# MR-71_RE0.net
KiCad netlist of a schematic drawn in Altium Designer
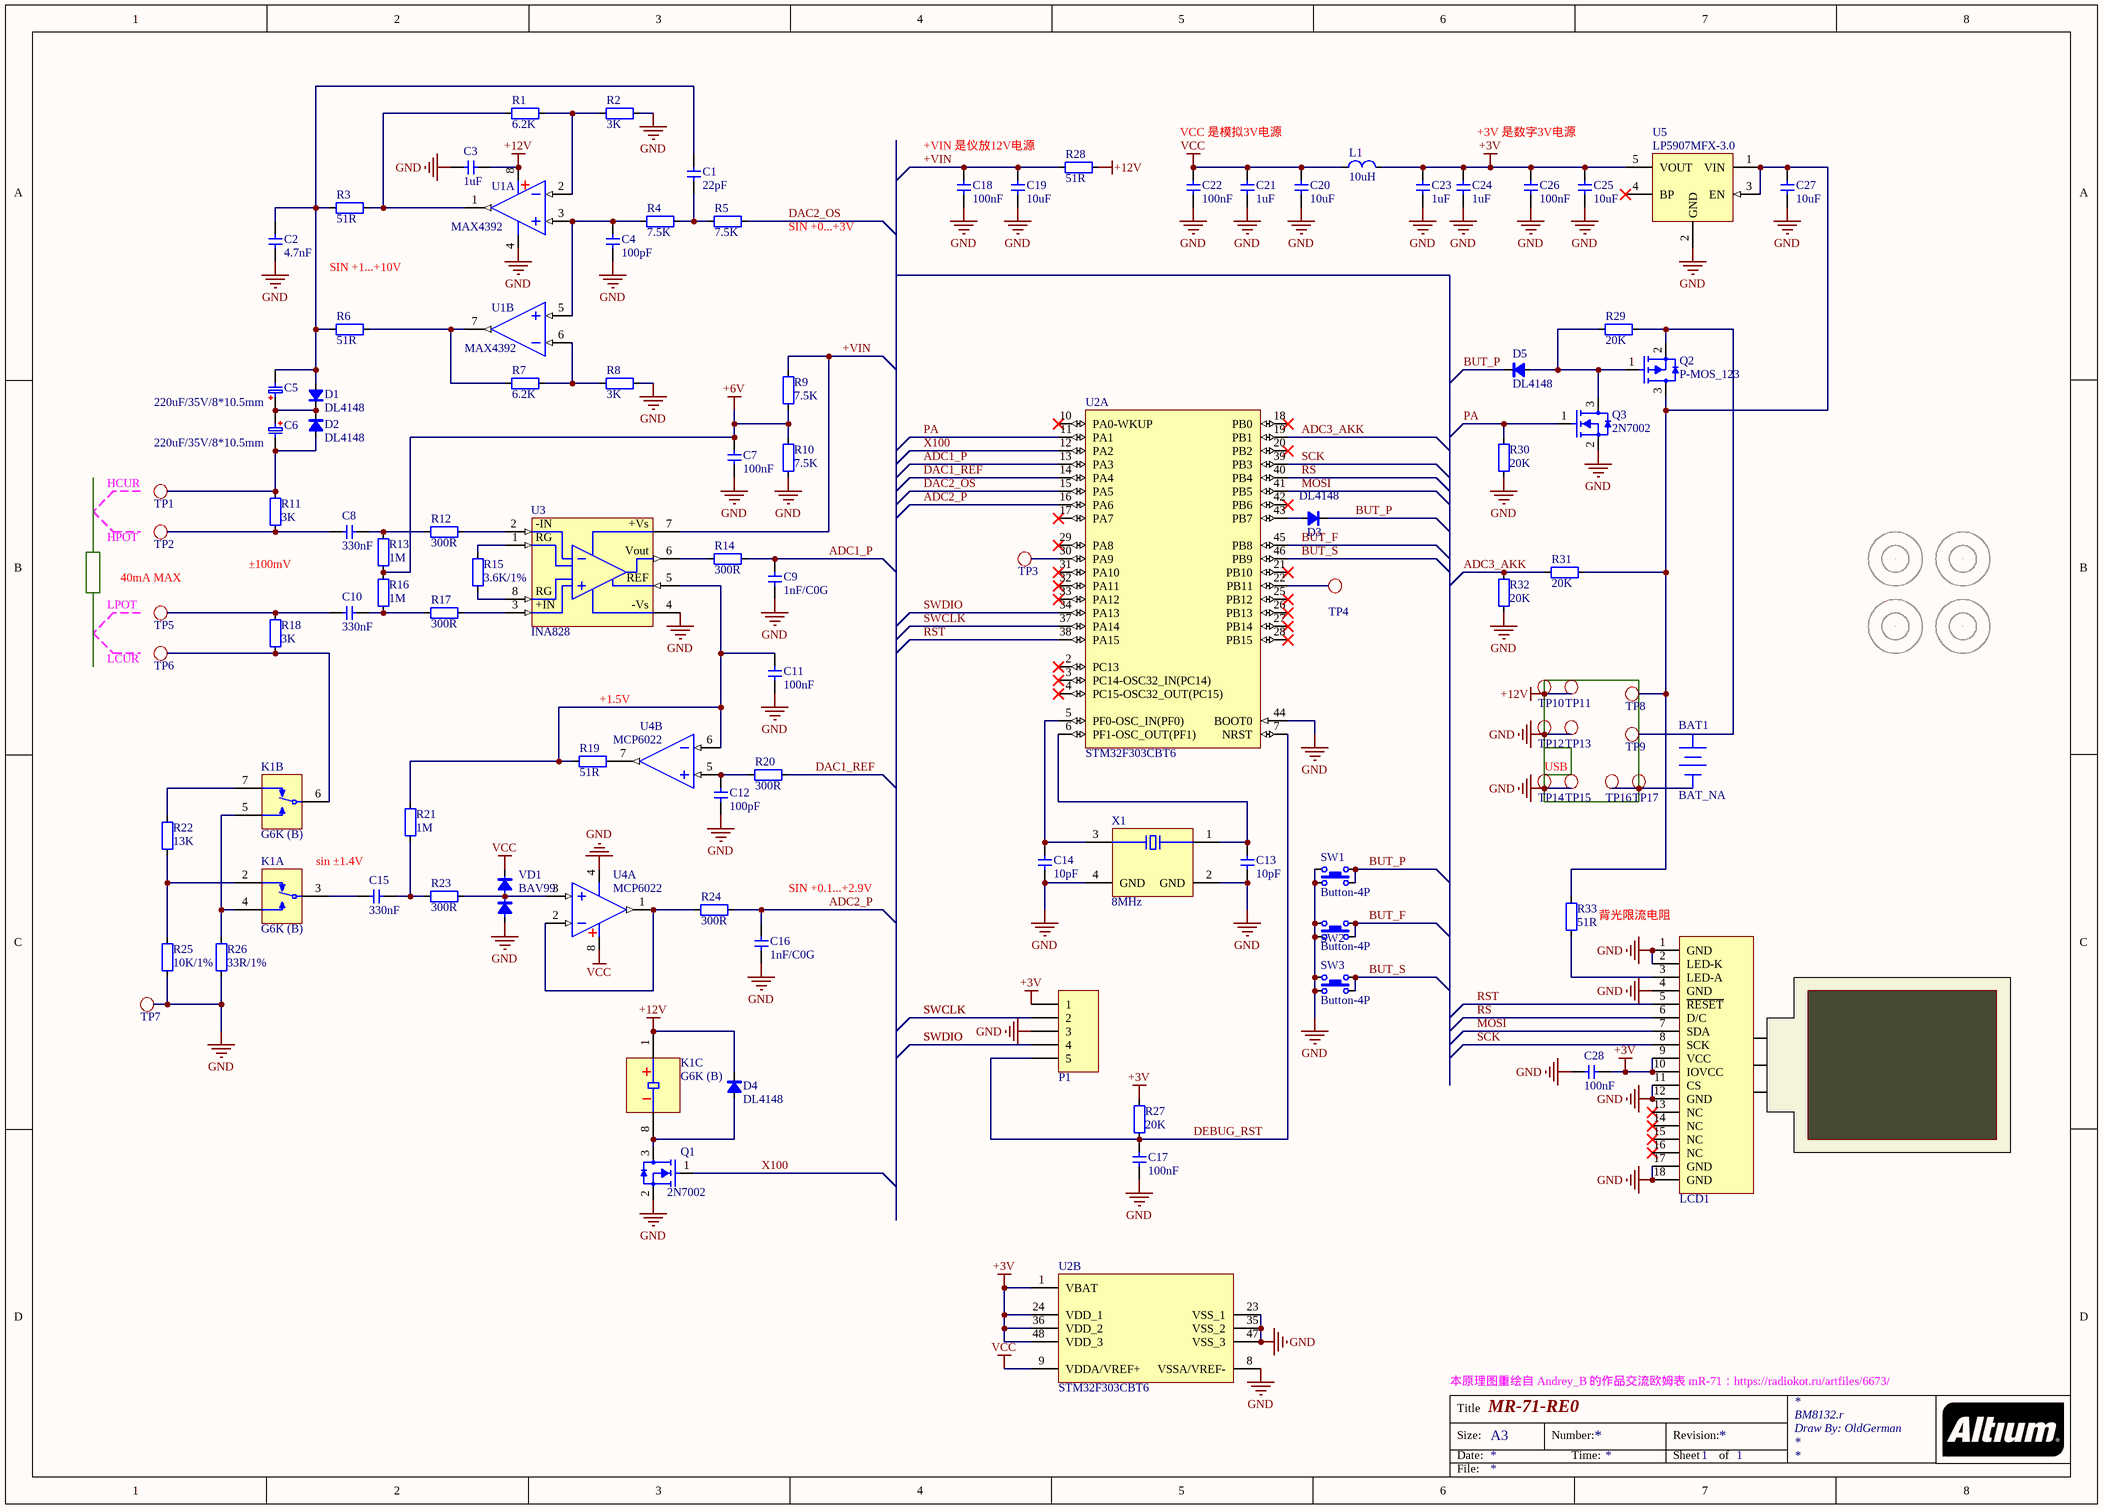
[diagram p0: MR-71_RE0.SchDoc]

(export (version "E")
  (design (tool "Eeschema 10.0.6"))
  (components
    (comp (ref "BAT1")
      (value "BAT_NA")
      (footprint "Lipo_NONE")
      (description "锂电池")
      (libsource (lib "ODG_AD_Lib") (part "BAT_NA"))
    )
    (comp (ref "C1")
      (value "22pF")
      (footprint "C0805")
      (description "Capacitor")
      (libsource (lib "ODG_AD_Lib") (part "CAP"))
    )
    (comp (ref "C2")
      (value "4.7nF")
      (footprint "C0805")
      (description "Capacitor")
      (libsource (lib "ODG_AD_Lib") (part "CAP"))
    )
    (comp (ref "C3")
      (value "1uF")
      (footprint "C0805")
      (description "Capacitor")
      (libsource (lib "ODG_AD_Lib") (part "CAP"))
    )
    (comp (ref "C4")
      (value "100pF")
      (footprint "C0805")
      (description "Capacitor")
      (libsource (lib "ODG_AD_Lib") (part "CAP"))
    )
    (comp (ref "C5")
      (value "220uF/35V/8*10.5mm")
      (footprint "CAP OS-CON D=8.0 L=11.9 E12")
      (description "Capacitor")
      (libsource (lib "ODG_AD_Lib") (part "CAP_Polar_Aluminum"))
    )
    (comp (ref "C6")
      (value "220uF/35V/8*10.5mm")
      (footprint "CAP OS-CON D=8.0 L=11.9 E12")
      (description "Capacitor")
      (libsource (lib "ODG_AD_Lib") (part "CAP_Polar_Aluminum"))
    )
    (comp (ref "C7")
      (value "100nF")
      (footprint "C0805")
      (description "Capacitor")
      (libsource (lib "ODG_AD_Lib") (part "CAP"))
    )
    (comp (ref "C8")
      (value "330nF")
      (footprint "C0805")
      (description "Capacitor")
      (libsource (lib "ODG_AD_Lib") (part "CAP"))
    )
    (comp (ref "C9")
      (value "1nF/C0G")
      (footprint "C0805")
      (description "Capacitor")
      (libsource (lib "ODG_AD_Lib") (part "CAP"))
    )
    (comp (ref "C10")
      (value "330nF")
      (footprint "C0805")
      (description "Capacitor")
      (libsource (lib "ODG_AD_Lib") (part "CAP"))
    )
    (comp (ref "C11")
      (value "100nF")
      (footprint "C0805")
      (description "Capacitor")
      (libsource (lib "ODG_AD_Lib") (part "CAP"))
    )
    (comp (ref "C12")
      (value "100pF")
      (footprint "C0805")
      (description "Capacitor")
      (libsource (lib "ODG_AD_Lib") (part "CAP"))
    )
    (comp (ref "C13")
      (value "10pF")
      (footprint "C0805")
      (description "Capacitor")
      (libsource (lib "ODG_AD_Lib") (part "CAP"))
    )
    (comp (ref "C14")
      (value "10pF")
      (footprint "C0805")
      (description "Capacitor")
      (libsource (lib "ODG_AD_Lib") (part "CAP"))
    )
    (comp (ref "C15")
      (value "330nF")
      (footprint "C0805")
      (description "Capacitor")
      (libsource (lib "ODG_AD_Lib") (part "CAP"))
    )
    (comp (ref "C16")
      (value "1nF/C0G")
      (footprint "C0805")
      (description "Capacitor")
      (libsource (lib "ODG_AD_Lib") (part "CAP"))
    )
    (comp (ref "C17")
      (value "100nF")
      (footprint "C0805")
      (description "Capacitor")
      (libsource (lib "ODG_AD_Lib") (part "CAP"))
    )
    (comp (ref "C18")
      (value "100nF")
      (footprint "C0805")
      (description "Capacitor")
      (libsource (lib "ODG_AD_Lib") (part "CAP"))
    )
    (comp (ref "C19")
      (value "10uF")
      (footprint "C1206")
      (description "Capacitor")
      (libsource (lib "ODG_AD_Lib") (part "CAP"))
    )
    (comp (ref "C20")
      (value "10uF")
      (footprint "C1206")
      (description "Capacitor")
      (libsource (lib "ODG_AD_Lib") (part "CAP"))
    )
    (comp (ref "C21")
      (value "1uF")
      (footprint "C0805")
      (description "Capacitor")
      (libsource (lib "ODG_AD_Lib") (part "CAP"))
    )
    (comp (ref "C22")
      (value "100nF")
      (footprint "C0805")
      (description "Capacitor")
      (libsource (lib "ODG_AD_Lib") (part "CAP"))
    )
    (comp (ref "C23")
      (value "1uF")
      (footprint "C0805")
      (description "Capacitor")
      (libsource (lib "ODG_AD_Lib") (part "CAP"))
    )
    (comp (ref "C24")
      (value "1uF")
      (footprint "C0805")
      (description "Capacitor")
      (libsource (lib "ODG_AD_Lib") (part "CAP"))
    )
    (comp (ref "C25")
      (value "10uF")
      (footprint "C1206")
      (description "Capacitor")
      (libsource (lib "ODG_AD_Lib") (part "CAP"))
    )
    (comp (ref "C26")
      (value "100nF")
      (footprint "C0805")
      (description "Capacitor")
      (libsource (lib "ODG_AD_Lib") (part "CAP"))
    )
    (comp (ref "C27")
      (value "10uF")
      (footprint "C1206")
      (description "Capacitor")
      (libsource (lib "ODG_AD_Lib") (part "CAP"))
    )
    (comp (ref "C28")
      (value "100nF")
      (footprint "C0805")
      (description "Capacitor")
      (libsource (lib "ODG_AD_Lib") (part "CAP"))
    )
    (comp (ref "D1")
      (value "DL4148")
      (footprint "SOD-123")
      (description "二极管")
      (libsource (lib "") (part "DIODE_1"))
    )
    (comp (ref "D2")
      (value "DL4148")
      (footprint "SOD-123")
      (description "二极管")
      (libsource (lib "") (part "DIODE_2"))
    )
    (comp (ref "D3")
      (value "DL4148")
      (footprint "SOD-123")
      (description "二极管")
      (libsource (lib "") (part "DIODE_3"))
    )
    (comp (ref "D4")
      (value "DL4148")
      (footprint "SOD-123")
      (description "二极管")
      (libsource (lib "") (part "DIODE_2"))
    )
    (comp (ref "D5")
      (value "DL4148")
      (footprint "SOD-123")
      (description "二极管")
      (libsource (lib "ODG_AD_Lib") (part "DIODE"))
    )
    (comp (ref "H1") (value "HOLE") (footprint "M3.1 D=5.8 SUN") (libsource (lib "ODG_AD_Lib") (part "HOLE")))
    (comp (ref "H2") (value "HOLE") (footprint "M3.1 D=5.8 SUN") (libsource (lib "ODG_AD_Lib") (part "HOLE")))
    (comp (ref "H3") (value "HOLE") (footprint "M3.1 D=5.8 SUN") (libsource (lib "ODG_AD_Lib") (part "HOLE")))
    (comp (ref "H4") (value "HOLE") (footprint "M3.1 D=5.8 SUN") (libsource (lib "ODG_AD_Lib") (part "HOLE")))
    (comp (ref "K1")
      (value "G6K (B)")
      (footprint "RELAY_G6K-2F-Y")
      (description "Telecom Relay DPDT (2 Form C) Surface Mount")
      (fields (field (name "MF") "Omron Electronics") (field (name "MP") "G6K-2F DC3"))
      (libsource (lib "ODG_AD_Lib") (part "G6K (B)"))
    )
    (comp (ref "L1")
      (value "10uH")
      (footprint "FER0805")
      (description "贴片叠层电感")
      (libsource (lib "ODG_AD_Lib") (part "inductor_mini"))
    )
    (comp (ref "LCD1")
      (value "LCD_Universal_128x160_18pin")
      (footprint "LCD-128X160-1.8INCH_SOLDER_MR-71")
      (libsource (lib "ODG_AD_Lib") (part "LCD_Universal_128x160_18pin"))
    )
    (comp (ref "P1")
      (value "CONN_X5")
      (footprint "2.54MM_MALE_X5")
      (libsource (lib "ODG_AD_Lib") (part "CONN_X5"))
    )
    (comp (ref "Q1")
      (value "2N7002")
      (footprint "INFINEON SOT-23-3")
      (description "N-MOS")
      (libsource (lib "ODG_AD_Lib") (part "N-MOS_123"))
    )
    (comp (ref "Q2")
      (value "P-MOS_123")
      (footprint "INFINEON SOT-23-3")
      (description "P-MOS")
      (libsource (lib "ODG_AD_Lib") (part "P-MOS_123"))
    )
    (comp (ref "Q3")
      (value "2N7002")
      (footprint "INFINEON SOT-23-3")
      (description "N-MOS")
      (libsource (lib "ODG_AD_Lib") (part "N-MOS_123"))
    )
    (comp (ref "R1")
      (value "6.2K")
      (footprint "R0805")
      (description "IEC Standard")
      (libsource (lib "") (part "RES_3"))
    )
    (comp (ref "R2")
      (value "3K")
      (footprint "R0805")
      (description "IEC Standard")
      (libsource (lib "") (part "RES_3"))
    )
    (comp (ref "R3")
      (value "51R")
      (footprint "R0805")
      (description "IEC Standard")
      (libsource (lib "") (part "RES_3"))
    )
    (comp (ref "R4")
      (value "7.5K")
      (footprint "R0805")
      (description "IEC Standard")
      (libsource (lib "") (part "RES_3"))
    )
    (comp (ref "R5")
      (value "7.5K")
      (footprint "R0805")
      (description "IEC Standard")
      (libsource (lib "") (part "RES_3"))
    )
    (comp (ref "R6")
      (value "51R")
      (footprint "R0805")
      (description "IEC Standard")
      (libsource (lib "ODG_AD_Lib") (part "RES"))
    )
    (comp (ref "R7")
      (value "6.2K")
      (footprint "R0805")
      (description "IEC Standard")
      (libsource (lib "ODG_AD_Lib") (part "RES"))
    )
    (comp (ref "R8")
      (value "3K")
      (footprint "R0805")
      (description "IEC Standard")
      (libsource (lib "ODG_AD_Lib") (part "RES"))
    )
    (comp (ref "R9")
      (value "7.5K")
      (footprint "R0805")
      (description "IEC Standard")
      (libsource (lib "ODG_AD_Lib") (part "RES"))
    )
    (comp (ref "R10")
      (value "7.5K")
      (footprint "R0805")
      (description "IEC Standard")
      (libsource (lib "ODG_AD_Lib") (part "RES"))
    )
    (comp (ref "R11")
      (value "3K")
      (footprint "R0805")
      (description "IEC Standard")
      (libsource (lib "") (part "RES_2"))
    )
    (comp (ref "R12")
      (value "300R")
      (footprint "R0805")
      (description "IEC Standard")
      (libsource (lib "") (part "RES_1"))
    )
    (comp (ref "R13")
      (value "1M")
      (footprint "R0805")
      (description "IEC Standard")
      (libsource (lib "") (part "RES_2"))
    )
    (comp (ref "R14")
      (value "300R")
      (footprint "R0805")
      (description "IEC Standard")
      (libsource (lib "") (part "RES_1"))
    )
    (comp (ref "R15")
      (value "3.6K/1%")
      (footprint "R0805")
      (description "IEC Standard")
      (libsource (lib "") (part "RES_2"))
    )
    (comp (ref "R16")
      (value "1M")
      (footprint "R0805")
      (description "IEC Standard")
      (libsource (lib "") (part "RES_2"))
    )
    (comp (ref "R17")
      (value "300R")
      (footprint "R0805")
      (description "IEC Standard")
      (libsource (lib "") (part "RES_1"))
    )
    (comp (ref "R18")
      (value "3K")
      (footprint "R0805")
      (description "IEC Standard")
      (libsource (lib "") (part "RES_2"))
    )
    (comp (ref "R19")
      (value "51R")
      (footprint "R0805")
      (description "IEC Standard")
      (libsource (lib "ODG_AD_Lib") (part "RES"))
    )
    (comp (ref "R20")
      (value "300R")
      (footprint "R0805")
      (description "IEC Standard")
      (libsource (lib "") (part "RES_1"))
    )
    (comp (ref "R21")
      (value "1M")
      (footprint "R0805")
      (description "IEC Standard")
      (libsource (lib "") (part "RES_2"))
    )
    (comp (ref "R22")
      (value "13K")
      (footprint "R0805")
      (description "IEC Standard")
      (libsource (lib "") (part "RES_2"))
    )
    (comp (ref "R23")
      (value "300R")
      (footprint "R0805")
      (description "IEC Standard")
      (libsource (lib "") (part "RES_1"))
    )
    (comp (ref "R24")
      (value "300R")
      (footprint "R0805")
      (description "IEC Standard")
      (libsource (lib "") (part "RES_1"))
    )
    (comp (ref "R25")
      (value "10K/1%")
      (footprint "R0805")
      (description "IEC Standard")
      (libsource (lib "") (part "RES_2"))
    )
    (comp (ref "R26")
      (value "33R/1%")
      (footprint "R1206")
      (description "IEC Standard")
      (libsource (lib "") (part "RES_2"))
    )
    (comp (ref "R27")
      (value "20K")
      (footprint "R0805")
      (description "IEC Standard")
      (libsource (lib "") (part "RES_3"))
    )
    (comp (ref "R28")
      (value "51R")
      (footprint "R0805")
      (description "IEC Standard")
      (libsource (lib "ODG_AD_Lib") (part "RES"))
    )
    (comp (ref "R29")
      (value "20K")
      (footprint "R0805")
      (description "IEC Standard")
      (libsource (lib "ODG_AD_Lib") (part "RES"))
    )
    (comp (ref "R30")
      (value "20K")
      (footprint "R0805")
      (description "IEC Standard")
      (libsource (lib "") (part "RES_2"))
    )
    (comp (ref "R31")
      (value "20K")
      (footprint "R0805")
      (description "IEC Standard")
      (libsource (lib "ODG_AD_Lib") (part "RES"))
    )
    (comp (ref "R32")
      (value "20K")
      (footprint "R0805")
      (description "IEC Standard")
      (libsource (lib "") (part "RES_2"))
    )
    (comp (ref "R33")
      (value "51R")
      (footprint "R0805")
      (description "IEC Standard")
      (libsource (lib "") (part "RES_3"))
    )
    (comp (ref "SW1")
      (value "Button-4P")
      (footprint "TACTILE_SWITCH_SMD_4X4MM")
      (description "Button")
      (libsource (lib "ODG_AD_Lib") (part "Button-4P"))
    )
    (comp (ref "SW2")
      (value "Button-4P")
      (footprint "TACTILE_SWITCH_SMD_4X4MM")
      (description "Button")
      (libsource (lib "ODG_AD_Lib") (part "Button-4P"))
    )
    (comp (ref "SW3")
      (value "Button-4P")
      (footprint "TACTILE_SWITCH_SMD_4X4MM")
      (description "Button")
      (libsource (lib "ODG_AD_Lib") (part "Button-4P"))
    )
    (comp (ref "TP1")
      (value "TP_SMD")
      (footprint "TP_SMD_1.5mm_01")
      (description "SMD testpad")
      (libsource (lib "ODG_AD_Lib") (part "TP_SMD"))
    )
    (comp (ref "TP2")
      (value "TP_SMD")
      (footprint "TP_SMD_1.5mm_01")
      (description "SMD testpad")
      (libsource (lib "ODG_AD_Lib") (part "TP_SMD"))
    )
    (comp (ref "TP3")
      (value "TP_SMD")
      (footprint "TP_SMD_1.5mm_01")
      (description "SMD testpad")
      (libsource (lib "ODG_AD_Lib") (part "TP_SMD"))
    )
    (comp (ref "TP4")
      (value "TP_SMD")
      (footprint "TP_SMD_1.5mm_01")
      (description "SMD testpad")
      (libsource (lib "ODG_AD_Lib") (part "TP_SMD"))
    )
    (comp (ref "TP5")
      (value "TP_SMD")
      (footprint "TP_SMD_1.5mm_01")
      (description "SMD testpad")
      (libsource (lib "ODG_AD_Lib") (part "TP_SMD"))
    )
    (comp (ref "TP6")
      (value "TP_SMD")
      (footprint "TP_SMD_1.5mm_01")
      (description "SMD testpad")
      (libsource (lib "ODG_AD_Lib") (part "TP_SMD"))
    )
    (comp (ref "TP7")
      (value "TP_SMD")
      (footprint "TP_SMD_1.5mm_01")
      (description "SMD testpad")
      (libsource (lib "ODG_AD_Lib") (part "TP_SMD"))
    )
    (comp (ref "TP8")
      (value "TP_SMD")
      (footprint "TP_SMD_1.5mm_01")
      (description "SMD testpad")
      (libsource (lib "ODG_AD_Lib") (part "TP_SMD"))
    )
    (comp (ref "TP9")
      (value "TP_SMD")
      (footprint "TP_SMD_1.5mm_01")
      (description "SMD testpad")
      (libsource (lib "ODG_AD_Lib") (part "TP_SMD"))
    )
    (comp (ref "TP10")
      (value "TP_SMD")
      (footprint "KEYSTONE_5015")
      (description "SMD testpad")
      (libsource (lib "ODG_AD_Lib") (part "TP_SMD"))
    )
    (comp (ref "TP11")
      (value "TP_SMD")
      (footprint "KEYSTONE_5015")
      (description "SMD testpad")
      (libsource (lib "ODG_AD_Lib") (part "TP_SMD"))
    )
    (comp (ref "TP12")
      (value "TP_SMD")
      (footprint "KEYSTONE_5015")
      (description "SMD testpad")
      (libsource (lib "ODG_AD_Lib") (part "TP_SMD"))
    )
    (comp (ref "TP13")
      (value "TP_SMD")
      (footprint "KEYSTONE_5015")
      (description "SMD testpad")
      (libsource (lib "ODG_AD_Lib") (part "TP_SMD"))
    )
    (comp (ref "TP14")
      (value "TP_SMD")
      (footprint "KEYSTONE_5015")
      (description "SMD testpad")
      (libsource (lib "ODG_AD_Lib") (part "TP_SMD"))
    )
    (comp (ref "TP15")
      (value "TP_SMD")
      (footprint "KEYSTONE_5015")
      (description "SMD testpad")
      (libsource (lib "ODG_AD_Lib") (part "TP_SMD"))
    )
    (comp (ref "TP16")
      (value "TP_SMD")
      (footprint "KEYSTONE_5015")
      (description "SMD testpad")
      (libsource (lib "ODG_AD_Lib") (part "TP_SMD"))
    )
    (comp (ref "TP17")
      (value "TP_SMD")
      (footprint "KEYSTONE_5015")
      (description "SMD testpad")
      (libsource (lib "ODG_AD_Lib") (part "TP_SMD"))
    )
    (comp (ref "U1")
      (value "MAX4392")
      (footprint "ANALOG DEV SOIC-8 R8")
      (description "通用型CMOS双路轨到轨放大器\r\nGeneral-Purpose CMOS Dual Rail-to-Rail Amplifier")
      (libsource (lib "ODG_AD_Lib") (part "AD8542"))
    )
    (comp (ref "U2")
      (value "STM32F303CBT6")
      (footprint "ST LQFP-48 7x7MM")
      (description "带DSP和FPU的主流混合信号ARM Cortex-M4 MCU，具有128 KB Flash、72 MHz CPU、MPU、CCM、5 MSPS 12位ADC、PGA和比较器")
      (fields (field (name "PARTNUMBER") "STM32F103CBT6"))
      (libsource (lib "ODG_AD_Lib") (part "STM32F303CBT6"))
    )
    (comp (ref "U3")
      (value "INA828")
      (footprint "ANALOG DEV SOIC-8 R8")
      (description "50-µV Offset, 7-nV/√Hz Noise, Low-Power, Precision Instrumentation Amplifier")
      (libsource (lib "ODG_AD_Lib") (part "INA828"))
    )
    (comp (ref "U4")
      (value "MCP6022")
      (footprint "ANALOG DEV SOIC-8 R8")
      (libsource (lib "ODG_AD_Lib") (part "AD8542"))
    )
    (comp (ref "U5")
      (value "LP5907MFX-3.0")
      (footprint "ANALOG TSOT-23-5 UJ-5")
      (description "超低噪声线性稳压芯片")
      (libsource (lib "ODG_AD_Lib") (part "ADP150AUJZ-3.3-R7"))
    )
    (comp (ref "VD1")
      (value "BAV99")
      (footprint "INFINEON SOT-23-3")
      (description "Dual Series Switching Diodes")
      (libsource (lib "ODG_AD_Lib") (part "BAV99"))
    )
    (comp (ref "X1")
      (value "8MHz")
      (footprint "EPSON TSX-3225")
      (description "4脚无源石英晶振")
      (libsource (lib "ODG_AD_Lib") (part "XTAL-4P_crystal"))
    )
  )
  (nets
    (net (code "1") (name "+3V") (class "Default")
      (node (ref "C23") (pin "1") (pinfunction "1_1") (pintype "passive"))
      (node (ref "C24") (pin "1") (pinfunction "1_1") (pintype "passive"))
      (node (ref "C25") (pin "1") (pinfunction "1_1") (pintype "passive"))
      (node (ref "C26") (pin "1") (pinfunction "1_1") (pintype "passive"))
      (node (ref "C28") (pin "2") (pinfunction "2_2") (pintype "passive"))
      (node (ref "L1") (pin "2") (pinfunction "2_2") (pintype "passive"))
      (node (ref "LCD1") (pin "10") (pinfunction "IOVCC_10") (pintype "passive"))
      (node (ref "LCD1") (pin "9") (pinfunction "VCC_9") (pintype "passive"))
      (node (ref "P1") (pin "1") (pinfunction "1_1") (pintype "passive"))
      (node (ref "R27") (pin "2") (pinfunction "2_2") (pintype "passive"))
      (node (ref "U2") (pin "1") (pinfunction "VBAT_1") (pintype "power_in"))
      (node (ref "U2") (pin "24") (pinfunction "VDD_1_24") (pintype "power_in"))
      (node (ref "U2") (pin "36") (pinfunction "VDD_2_36") (pintype "power_in"))
      (node (ref "U2") (pin "48") (pinfunction "VDD_3_48") (pintype "power_in"))
      (node (ref "U5") (pin "5") (pinfunction "VOUT_5") (pintype "passive"))
    )
    (net (code "2") (name "+6V") (class "Default")
      (node (ref "C7") (pin "1") (pinfunction "1_1") (pintype "passive"))
      (node (ref "R10") (pin "2") (pinfunction "2_2") (pintype "passive"))
      (node (ref "R13") (pin "2") (pinfunction "2_2") (pintype "passive"))
      (node (ref "R16") (pin "1") (pinfunction "1_1") (pintype "passive"))
      (node (ref "R9") (pin "1") (pinfunction "1_1") (pintype "passive"))
    )
    (net (code "3") (name "+12V") (class "Default")
      (node (ref "C3") (pin "2") (pinfunction "2_2") (pintype "passive"))
      (node (ref "D4") (pin "2") (pinfunction "C_2") (pintype "passive"))
      (node (ref "K1") (pin "1") (pinfunction "1_1") (pintype "passive"))
      (node (ref "R28") (pin "2") (pinfunction "2_2") (pintype "passive"))
      (node (ref "TP10") (pin "1") (pinfunction "1_1") (pintype "passive"))
      (node (ref "TP11") (pin "1") (pinfunction "1_1") (pintype "passive"))
      (node (ref "U1") (pin "8") (pinfunction "V+_8") (pintype "power_in"))
    )
    (net (code "4") (name "/+VIN") (class "Default")
      (node (ref "C18") (pin "1") (pinfunction "1_1") (pintype "passive"))
      (node (ref "C19") (pin "1") (pinfunction "1_1") (pintype "passive"))
      (node (ref "R28") (pin "1") (pinfunction "1_1") (pintype "passive"))
      (node (ref "R9") (pin "2") (pinfunction "2_2") (pintype "passive"))
      (node (ref "U3") (pin "7") (pinfunction "+Vs_7") (pintype "passive"))
    )
    (net (code "5") (name "/ADC1_P") (class "Default")
      (node (ref "C9") (pin "1") (pinfunction "1_1") (pintype "passive"))
      (node (ref "R14") (pin "1") (pinfunction "1_1") (pintype "passive"))
      (node (ref "U2") (pin "13") (pinfunction "PA3_13") (pintype "bidirectional"))
    )
    (net (code "6") (name "/ADC2_P") (class "Default")
      (node (ref "C16") (pin "2") (pinfunction "2_2") (pintype "passive"))
      (node (ref "R24") (pin "1") (pinfunction "1_1") (pintype "passive"))
      (node (ref "U2") (pin "16") (pinfunction "PA6_16") (pintype "bidirectional"))
    )
    (net (code "7") (name "/ADC3_AKK") (class "Default")
      (node (ref "R31") (pin "1") (pinfunction "1_1") (pintype "passive"))
      (node (ref "R32") (pin "1") (pinfunction "1_1") (pintype "passive"))
      (node (ref "U2") (pin "19") (pinfunction "PB1_19") (pintype "bidirectional"))
    )
    (net (code "8") (name "/BUT_F") (class "Default")
      (node (ref "SW2") (pin "3") (pinfunction "3_3") (pintype "passive"))
      (node (ref "SW2") (pin "4") (pinfunction "4_4") (pintype "passive"))
      (node (ref "U2") (pin "45") (pinfunction "PB8_45") (pintype "bidirectional"))
    )
    (net (code "9") (name "/BUT_P") (class "Default")
      (node (ref "D3") (pin "2") (pinfunction "C_2") (pintype "passive"))
      (node (ref "D5") (pin "2") (pinfunction "C_2") (pintype "passive"))
      (node (ref "SW1") (pin "3") (pinfunction "3_3") (pintype "passive"))
      (node (ref "SW1") (pin "4") (pinfunction "4_4") (pintype "passive"))
    )
    (net (code "10") (name "/BUT_S") (class "Default")
      (node (ref "SW3") (pin "3") (pinfunction "3_3") (pintype "passive"))
      (node (ref "SW3") (pin "4") (pinfunction "4_4") (pintype "passive"))
      (node (ref "U2") (pin "46") (pinfunction "PB9_46") (pintype "bidirectional"))
    )
    (net (code "11") (name "/DAC1_REF") (class "Default")
      (node (ref "R20") (pin "1") (pinfunction "1_1") (pintype "passive"))
      (node (ref "U2") (pin "14") (pinfunction "PA4_14") (pintype "bidirectional"))
    )
    (net (code "12") (name "/DAC2_OS") (class "Default")
      (node (ref "R5") (pin "2") (pinfunction "2_2") (pintype "passive"))
      (node (ref "U2") (pin "15") (pinfunction "PA5_15") (pintype "bidirectional"))
    )
    (net (code "13") (name "/DEBUG_RST") (class "Default")
      (node (ref "C17") (pin "2") (pinfunction "2_2") (pintype "passive"))
      (node (ref "P1") (pin "5") (pinfunction "5_5") (pintype "passive"))
      (node (ref "R27") (pin "1") (pinfunction "1_1") (pintype "passive"))
      (node (ref "U2") (pin "7") (pinfunction "NRST_7") (pintype "bidirectional"))
    )
    (net (code "14") (name "/MOSI") (class "Default")
      (node (ref "LCD1") (pin "7") (pinfunction "SDA_7") (pintype "passive"))
      (node (ref "U2") (pin "41") (pinfunction "PB5_41") (pintype "bidirectional"))
    )
    (net (code "15") (name "/PA") (class "Default")
      (node (ref "Q3") (pin "1") (pinfunction "G_1") (pintype "passive"))
      (node (ref "R30") (pin "1") (pinfunction "1_1") (pintype "passive"))
      (node (ref "U2") (pin "11") (pinfunction "PA1_11") (pintype "bidirectional"))
    )
    (net (code "16") (name "/RS") (class "Default")
      (node (ref "LCD1") (pin "6") (pinfunction "D/C_6") (pintype "passive"))
      (node (ref "U2") (pin "40") (pinfunction "PB4_40") (pintype "bidirectional"))
    )
    (net (code "17") (name "/RST") (class "Default")
      (node (ref "LCD1") (pin "5") (pinfunction "~{RESET}_5") (pintype "passive"))
      (node (ref "U2") (pin "38") (pinfunction "PA15_38") (pintype "bidirectional"))
    )
    (net (code "18") (name "/SCK") (class "Default")
      (node (ref "LCD1") (pin "8") (pinfunction "SCK_8") (pintype "passive"))
      (node (ref "U2") (pin "39") (pinfunction "PB3_39") (pintype "bidirectional"))
    )
    (net (code "19") (name "/SWCLK") (class "Default")
      (node (ref "P1") (pin "2") (pinfunction "2_2") (pintype "passive"))
      (node (ref "U2") (pin "37") (pinfunction "PA14_37") (pintype "bidirectional"))
    )
    (net (code "20") (name "/SWDIO") (class "Default")
      (node (ref "P1") (pin "4") (pinfunction "4_4") (pintype "passive"))
      (node (ref "U2") (pin "34") (pinfunction "PA13_34") (pintype "bidirectional"))
    )
    (net (code "21") (name "/X100") (class "Default")
      (node (ref "Q1") (pin "1") (pinfunction "G_1") (pintype "passive"))
      (node (ref "U2") (pin "12") (pinfunction "PA2_12") (pintype "bidirectional"))
    )
    (net (code "22") (name "GND") (class "Default")
      (node (ref "C11") (pin "2") (pinfunction "2_2") (pintype "passive"))
      (node (ref "C12") (pin "2") (pinfunction "2_2") (pintype "passive"))
      (node (ref "C13") (pin "1") (pinfunction "1_1") (pintype "passive"))
      (node (ref "C14") (pin "1") (pinfunction "1_1") (pintype "passive"))
      (node (ref "C16") (pin "1") (pinfunction "1_1") (pintype "passive"))
      (node (ref "C17") (pin "1") (pinfunction "1_1") (pintype "passive"))
      (node (ref "C18") (pin "2") (pinfunction "2_2") (pintype "passive"))
      (node (ref "C19") (pin "2") (pinfunction "2_2") (pintype "passive"))
      (node (ref "C2") (pin "2") (pinfunction "2_2") (pintype "passive"))
      (node (ref "C20") (pin "2") (pinfunction "2_2") (pintype "passive"))
      (node (ref "C21") (pin "2") (pinfunction "2_2") (pintype "passive"))
      (node (ref "C22") (pin "2") (pinfunction "2_2") (pintype "passive"))
      (node (ref "C23") (pin "2") (pinfunction "2_2") (pintype "passive"))
      (node (ref "C24") (pin "2") (pinfunction "2_2") (pintype "passive"))
      (node (ref "C25") (pin "2") (pinfunction "2_2") (pintype "passive"))
      (node (ref "C26") (pin "2") (pinfunction "2_2") (pintype "passive"))
      (node (ref "C27") (pin "2") (pinfunction "2_2") (pintype "passive"))
      (node (ref "C28") (pin "1") (pinfunction "1_1") (pintype "passive"))
      (node (ref "C3") (pin "1") (pinfunction "1_1") (pintype "passive"))
      (node (ref "C4") (pin "2") (pinfunction "2_2") (pintype "passive"))
      (node (ref "C7") (pin "2") (pinfunction "2_2") (pintype "passive"))
      (node (ref "C9") (pin "2") (pinfunction "2_2") (pintype "passive"))
      (node (ref "LCD1") (pin "1") (pinfunction "GND_1") (pintype "passive"))
      (node (ref "LCD1") (pin "11") (pinfunction "CS_11") (pintype "passive"))
      (node (ref "LCD1") (pin "12") (pinfunction "GND_12") (pintype "passive"))
      (node (ref "LCD1") (pin "17") (pinfunction "GND_17") (pintype "passive"))
      (node (ref "LCD1") (pin "18") (pinfunction "GND_18") (pintype "passive"))
      (node (ref "LCD1") (pin "2") (pinfunction "LED-K_2") (pintype "passive"))
      (node (ref "LCD1") (pin "4") (pinfunction "GND_4") (pintype "passive"))
      (node (ref "P1") (pin "3") (pinfunction "3_3") (pintype "passive"))
      (node (ref "Q1") (pin "2") (pinfunction "S_2") (pintype "passive"))
      (node (ref "Q3") (pin "2") (pinfunction "S_2") (pintype "passive"))
      (node (ref "R10") (pin "1") (pinfunction "1_1") (pintype "passive"))
      (node (ref "R2") (pin "2") (pinfunction "2_2") (pintype "passive"))
      (node (ref "R25") (pin "2") (pinfunction "2_2") (pintype "passive"))
      (node (ref "R26") (pin "2") (pinfunction "2_2") (pintype "passive"))
      (node (ref "R30") (pin "2") (pinfunction "2_2") (pintype "passive"))
      (node (ref "R32") (pin "2") (pinfunction "2_2") (pintype "passive"))
      (node (ref "R8") (pin "2") (pinfunction "2_2") (pintype "passive"))
      (node (ref "SW1") (pin "1") (pinfunction "1_1") (pintype "passive"))
      (node (ref "SW1") (pin "2") (pinfunction "2_2") (pintype "passive"))
      (node (ref "SW2") (pin "1") (pinfunction "1_1") (pintype "passive"))
      (node (ref "SW2") (pin "2") (pinfunction "2_2") (pintype "passive"))
      (node (ref "SW3") (pin "1") (pinfunction "1_1") (pintype "passive"))
      (node (ref "SW3") (pin "2") (pinfunction "2_2") (pintype "passive"))
      (node (ref "TP12") (pin "1") (pinfunction "1_1") (pintype "passive"))
      (node (ref "TP13") (pin "1") (pinfunction "1_1") (pintype "passive"))
      (node (ref "TP14") (pin "1") (pinfunction "1_1") (pintype "passive"))
      (node (ref "TP15") (pin "1") (pinfunction "1_1") (pintype "passive"))
      (node (ref "TP7") (pin "1") (pinfunction "1_1") (pintype "passive"))
      (node (ref "U1") (pin "4") (pinfunction "V-_4") (pintype "power_in"))
      (node (ref "U2") (pin "23") (pinfunction "VSS_1_23") (pintype "power_in"))
      (node (ref "U2") (pin "35") (pinfunction "VSS_2_35") (pintype "power_in"))
      (node (ref "U2") (pin "44") (pinfunction "BOOT0_44") (pintype "input"))
      (node (ref "U2") (pin "47") (pinfunction "VSS_3_47") (pintype "power_in"))
      (node (ref "U2") (pin "8") (pinfunction "VSSA/VREF-_8") (pintype "power_in"))
      (node (ref "U3") (pin "4") (pinfunction "-Vs_4") (pintype "passive"))
      (node (ref "U4") (pin "4") (pinfunction "V-_4") (pintype "power_in"))
      (node (ref "U5") (pin "2") (pinfunction "GND_2") (pintype "passive"))
      (node (ref "VD1") (pin "1") (pinfunction "1_1") (pintype "passive"))
      (node (ref "X1") (pin "2") (pinfunction "GND_2") (pintype "passive"))
      (node (ref "X1") (pin "4") (pinfunction "GND_4") (pintype "passive"))
    )
    (net (code "23") (name "Net-(C1-Pad2)") (class "Default")
      (node (ref "C1") (pin "2") (pinfunction "2_2") (pintype "passive"))
      (node (ref "R4") (pin "2") (pinfunction "2_2") (pintype "passive"))
      (node (ref "R5") (pin "1") (pinfunction "1_1") (pintype "passive"))
    )
    (net (code "24") (name "Net-(C8-Pad1)") (class "Default")
      (node (ref "C8") (pin "1") (pinfunction "1_1") (pintype "passive"))
      (node (ref "R12") (pin "2") (pinfunction "2_2") (pintype "passive"))
      (node (ref "R13") (pin "1") (pinfunction "1_1") (pintype "passive"))
    )
    (net (code "25") (name "Net-(C8-Pad2)") (class "Default")
      (node (ref "C8") (pin "2") (pinfunction "2_2") (pintype "passive"))
      (node (ref "R11") (pin "2") (pinfunction "2_2") (pintype "passive"))
      (node (ref "TP2") (pin "1") (pinfunction "1_1") (pintype "passive"))
    )
    (net (code "26") (name "Net-(C10-Pad1)") (class "Default")
      (node (ref "C10") (pin "1") (pinfunction "1_1") (pintype "passive"))
      (node (ref "R16") (pin "2") (pinfunction "2_2") (pintype "passive"))
      (node (ref "R17") (pin "2") (pinfunction "2_2") (pintype "passive"))
    )
    (net (code "27") (name "Net-(C10-Pad2)") (class "Default")
      (node (ref "C10") (pin "2") (pinfunction "2_2") (pintype "passive"))
      (node (ref "R18") (pin "1") (pinfunction "1_1") (pintype "passive"))
      (node (ref "TP5") (pin "1") (pinfunction "1_1") (pintype "passive"))
    )
    (net (code "28") (name "Net-(C15-Pad1)") (class "Default")
      (node (ref "C15") (pin "1") (pinfunction "1_1") (pintype "passive"))
      (node (ref "R21") (pin "2") (pinfunction "2_2") (pintype "passive"))
      (node (ref "R23") (pin "2") (pinfunction "2_2") (pintype "passive"))
    )
    (net (code "29") (name "Net-(C15-Pad2)") (class "Default")
      (node (ref "C15") (pin "2") (pinfunction "2_2") (pintype "passive"))
      (node (ref "K1") (pin "3") (pinfunction "3_3") (pintype "passive"))
    )
    (net (code "30") (name "Net-(D1-A)") (class "Default")
      (node (ref "C1") (pin "1") (pinfunction "1_1") (pintype "passive"))
      (node (ref "C2") (pin "1") (pinfunction "1_1") (pintype "passive"))
      (node (ref "C5") (pin "2") (pinfunction "2_2") (pintype "passive"))
      (node (ref "D1") (pin "1") (pinfunction "A_1") (pintype "passive"))
      (node (ref "R3") (pin "1") (pinfunction "1_1") (pintype "passive"))
      (node (ref "R6") (pin "1") (pinfunction "1_1") (pintype "passive"))
    )
    (net (code "31") (name "Net-(D1-C)") (class "Default")
      (node (ref "C5") (pin "1") (pinfunction "1_1") (pintype "passive"))
      (node (ref "C6") (pin "1") (pinfunction "1_1") (pintype "passive"))
      (node (ref "D1") (pin "2") (pinfunction "C_2") (pintype "passive"))
      (node (ref "D2") (pin "2") (pinfunction "C_2") (pintype "passive"))
    )
    (net (code "32") (name "Net-(D2-A)") (class "Default")
      (node (ref "C6") (pin "2") (pinfunction "2_2") (pintype "passive"))
      (node (ref "D2") (pin "1") (pinfunction "A_1") (pintype "passive"))
      (node (ref "R11") (pin "1") (pinfunction "1_1") (pintype "passive"))
      (node (ref "TP1") (pin "1") (pinfunction "1_1") (pintype "passive"))
    )
    (net (code "33") (name "Net-(D3-A)") (class "Default")
      (node (ref "D3") (pin "1") (pinfunction "A_1") (pintype "passive"))
      (node (ref "U2") (pin "43") (pinfunction "PB7_43") (pintype "bidirectional"))
    )
    (net (code "34") (name "Net-(D4-A)") (class "Default")
      (node (ref "D4") (pin "1") (pinfunction "A_1") (pintype "passive"))
      (node (ref "K1") (pin "8") (pinfunction "8_8") (pintype "passive"))
      (node (ref "Q1") (pin "3") (pinfunction "D_3") (pintype "passive"))
    )
    (net (code "35") (name "Net-(D5-A)") (class "Default")
      (node (ref "D5") (pin "1") (pinfunction "A_1") (pintype "passive"))
      (node (ref "Q2") (pin "1") (pinfunction "G_1") (pintype "passive"))
      (node (ref "Q3") (pin "3") (pinfunction "D_3") (pintype "passive"))
      (node (ref "R29") (pin "1") (pinfunction "1_1") (pintype "passive"))
    )
    (net (code "36") (name "Net-(K1-Pad2)") (class "Default")
      (node (ref "K1") (pin "2") (pinfunction "2_2") (pintype "passive"))
      (node (ref "R22") (pin "2") (pinfunction "2_2") (pintype "passive"))
      (node (ref "R25") (pin "1") (pinfunction "1_1") (pintype "passive"))
    )
    (net (code "37") (name "Net-(K1-Pad4)") (class "Default")
      (node (ref "K1") (pin "4") (pinfunction "4_4") (pintype "passive"))
      (node (ref "K1") (pin "5") (pinfunction "5_5") (pintype "passive"))
      (node (ref "R26") (pin "1") (pinfunction "1_1") (pintype "passive"))
    )
    (net (code "38") (name "Net-(K1-Pad6)") (class "Default")
      (node (ref "K1") (pin "6") (pinfunction "6_6") (pintype "passive"))
      (node (ref "R18") (pin "2") (pinfunction "2_2") (pintype "passive"))
      (node (ref "TP6") (pin "1") (pinfunction "1_1") (pintype "passive"))
    )
    (net (code "39") (name "Net-(K1-Pad7)") (class "Default")
      (node (ref "K1") (pin "7") (pinfunction "7_7") (pintype "passive"))
      (node (ref "R22") (pin "1") (pinfunction "1_1") (pintype "passive"))
    )
    (net (code "40") (name "Net-(LCD1-LED-A)") (class "Default")
      (node (ref "LCD1") (pin "3") (pinfunction "LED-A_3") (pintype "passive"))
      (node (ref "R33") (pin "1") (pinfunction "1_1") (pintype "passive"))
    )
    (net (code "41") (name "Net-(Q2-D)") (class "Default")
      (node (ref "C27") (pin "1") (pinfunction "1_1") (pintype "passive"))
      (node (ref "Q2") (pin "3") (pinfunction "D_3") (pintype "passive"))
      (node (ref "R31") (pin "2") (pinfunction "2_2") (pintype "passive"))
      (node (ref "R33") (pin "2") (pinfunction "2_2") (pintype "passive"))
      (node (ref "TP8") (pin "1") (pinfunction "1_1") (pintype "passive"))
      (node (ref "U5") (pin "1") (pinfunction "VIN_1") (pintype "passive"))
      (node (ref "U5") (pin "3") (pinfunction "EN_3") (pintype "input"))
    )
    (net (code "42") (name "Net-(Q2-S)") (class "Default")
      (node (ref "Q2") (pin "2") (pinfunction "S_2") (pintype "passive"))
      (node (ref "R29") (pin "2") (pinfunction "2_2") (pintype "passive"))
      (node (ref "TP9") (pin "1") (pinfunction "1_1") (pintype "passive"))
    )
    (net (code "43") (name "Net-(R15-Pad1)") (class "Default")
      (node (ref "R15") (pin "1") (pinfunction "1_1") (pintype "passive"))
      (node (ref "U3") (pin "1") (pinfunction "RG_1") (pintype "input"))
    )
    (net (code "44") (name "Net-(R15-Pad2)") (class "Default")
      (node (ref "R15") (pin "2") (pinfunction "2_2") (pintype "passive"))
      (node (ref "U3") (pin "8") (pinfunction "RG_8") (pintype "input"))
    )
    (net (code "45") (name "Net-(TP16-Pad1)") (class "Default")
      (node (ref "TP16") (pin "1") (pinfunction "1_1") (pintype "passive"))
      (node (ref "TP17") (pin "1") (pinfunction "1_1") (pintype "passive"))
    )
    (net (code "46") (name "Net-(U1A-+)") (class "Default")
      (node (ref "C4") (pin "1") (pinfunction "1_1") (pintype "passive"))
      (node (ref "R4") (pin "1") (pinfunction "1_1") (pintype "passive"))
      (node (ref "U1") (pin "3") (pinfunction "+_3") (pintype "input"))
      (node (ref "U1") (pin "5") (pinfunction "+_5") (pintype "input"))
    )
    (net (code "47") (name "Net-(U1A--)") (class "Default")
      (node (ref "R1") (pin "2") (pinfunction "2_2") (pintype "passive"))
      (node (ref "R2") (pin "1") (pinfunction "1_1") (pintype "passive"))
      (node (ref "U1") (pin "2") (pinfunction "-_2") (pintype "input"))
    )
    (net (code "48") (name "Net-(U1A-OUT1)") (class "Default")
      (node (ref "R1") (pin "1") (pinfunction "1_1") (pintype "passive"))
      (node (ref "R3") (pin "2") (pinfunction "2_2") (pintype "passive"))
      (node (ref "U1") (pin "1") (pinfunction "OUT1_1") (pintype "output"))
    )
    (net (code "49") (name "Net-(U1B--)") (class "Default")
      (node (ref "R7") (pin "2") (pinfunction "2_2") (pintype "passive"))
      (node (ref "R8") (pin "1") (pinfunction "1_1") (pintype "passive"))
      (node (ref "U1") (pin "6") (pinfunction "-_6") (pintype "input"))
    )
    (net (code "50") (name "Net-(U1B-OUT2)") (class "Default")
      (node (ref "R6") (pin "2") (pinfunction "2_2") (pintype "passive"))
      (node (ref "R7") (pin "1") (pinfunction "1_1") (pintype "passive"))
      (node (ref "U1") (pin "7") (pinfunction "OUT2_7") (pintype "output"))
    )
    (net (code "51") (name "Net-(U2A-PA9)") (class "Default")
      (node (ref "TP3") (pin "1") (pinfunction "1_1") (pintype "passive"))
      (node (ref "U2") (pin "30") (pinfunction "PA9_30") (pintype "bidirectional"))
    )
    (net (code "52") (name "Net-(U2A-PB11)") (class "Default")
      (node (ref "TP4") (pin "1") (pinfunction "1_1") (pintype "passive"))
      (node (ref "U2") (pin "22") (pinfunction "PB11_22") (pintype "bidirectional"))
    )
    (net (code "53") (name "Net-(U2A-PF0-OSC_IN(PF0))") (class "Default")
      (node (ref "C14") (pin "2") (pinfunction "2_2") (pintype "passive"))
      (node (ref "U2") (pin "5") (pinfunction "PF0-OSC_IN(PF0)_5") (pintype "bidirectional"))
      (node (ref "X1") (pin "3") (pinfunction "3_3") (pintype "passive"))
    )
    (net (code "54") (name "Net-(U2A-PF1-OSC_OUT(PF1))") (class "Default")
      (node (ref "C13") (pin "2") (pinfunction "2_2") (pintype "passive"))
      (node (ref "U2") (pin "6") (pinfunction "PF1-OSC_OUT(PF1)_6") (pintype "bidirectional"))
      (node (ref "X1") (pin "1") (pinfunction "1_1") (pintype "passive"))
    )
    (net (code "55") (name "Net-(U3-+IN)") (class "Default")
      (node (ref "R17") (pin "1") (pinfunction "1_1") (pintype "passive"))
      (node (ref "U3") (pin "3") (pinfunction "+IN_3") (pintype "input"))
    )
    (net (code "56") (name "Net-(U3--IN)") (class "Default")
      (node (ref "R12") (pin "1") (pinfunction "1_1") (pintype "passive"))
      (node (ref "U3") (pin "2") (pinfunction "-IN_2") (pintype "input"))
    )
    (net (code "57") (name "Net-(U3-REF)") (class "Default")
      (node (ref "C11") (pin "1") (pinfunction "1_1") (pintype "passive"))
      (node (ref "R19") (pin "1") (pinfunction "1_1") (pintype "passive"))
      (node (ref "R21") (pin "1") (pinfunction "1_1") (pintype "passive"))
      (node (ref "U3") (pin "5") (pinfunction "REF_5") (pintype "input"))
      (node (ref "U4") (pin "6") (pinfunction "-_6") (pintype "input"))
    )
    (net (code "58") (name "Net-(U3-Vout)") (class "Default")
      (node (ref "R14") (pin "2") (pinfunction "2_2") (pintype "passive"))
      (node (ref "U3") (pin "6") (pinfunction "Vout_6") (pintype "output"))
    )
    (net (code "59") (name "Net-(U4A-+)") (class "Default")
      (node (ref "R23") (pin "1") (pinfunction "1_1") (pintype "passive"))
      (node (ref "U4") (pin "3") (pinfunction "+_3") (pintype "input"))
      (node (ref "VD1") (pin "3") (pinfunction "3_3") (pintype "passive"))
    )
    (net (code "60") (name "Net-(U4A--)") (class "Default")
      (node (ref "R24") (pin "2") (pinfunction "2_2") (pintype "passive"))
      (node (ref "U4") (pin "1") (pinfunction "OUT1_1") (pintype "output"))
      (node (ref "U4") (pin "2") (pinfunction "-_2") (pintype "input"))
    )
    (net (code "61") (name "Net-(U4B-+)") (class "Default")
      (node (ref "C12") (pin "1") (pinfunction "1_1") (pintype "passive"))
      (node (ref "R20") (pin "2") (pinfunction "2_2") (pintype "passive"))
      (node (ref "U4") (pin "5") (pinfunction "+_5") (pintype "input"))
    )
    (net (code "62") (name "Net-(U4B-OUT2)") (class "Default")
      (node (ref "R19") (pin "2") (pinfunction "2_2") (pintype "passive"))
      (node (ref "U4") (pin "7") (pinfunction "OUT2_7") (pintype "output"))
    )
    (net (code "63") (name "VCC") (class "Default")
      (node (ref "C20") (pin "1") (pinfunction "1_1") (pintype "passive"))
      (node (ref "C21") (pin "1") (pinfunction "1_1") (pintype "passive"))
      (node (ref "C22") (pin "1") (pinfunction "1_1") (pintype "passive"))
      (node (ref "L1") (pin "1") (pinfunction "1_1") (pintype "passive"))
      (node (ref "U2") (pin "9") (pinfunction "VDDA/VREF+_9") (pintype "power_in"))
      (node (ref "U4") (pin "8") (pinfunction "V+_8") (pintype "power_in"))
      (node (ref "VD1") (pin "2") (pinfunction "2_2") (pintype "passive"))
    )
    (net (code "64") (name "unconnected-(H1-Pad1)") (class "Default")
      (node (ref "H1") (pin "1") (pinfunction "1_1") (pintype "passive"))
    )
    (net (code "65") (name "unconnected-(H2-Pad1)") (class "Default")
      (node (ref "H2") (pin "1") (pinfunction "1_1") (pintype "passive"))
    )
    (net (code "66") (name "unconnected-(H3-Pad1)") (class "Default")
      (node (ref "H3") (pin "1") (pinfunction "1_1") (pintype "passive"))
    )
    (net (code "67") (name "unconnected-(H4-Pad1)") (class "Default")
      (node (ref "H4") (pin "1") (pinfunction "1_1") (pintype "passive"))
    )
    (net (code "68") (name "unconnected-(LCD1-NC-Pad13)") (class "Default")
      (node (ref "LCD1") (pin "13") (pinfunction "NC_13") (pintype "passive+no_connect"))
    )
    (net (code "69") (name "unconnected-(LCD1-NC-Pad14)") (class "Default")
      (node (ref "LCD1") (pin "14") (pinfunction "NC_14") (pintype "passive+no_connect"))
    )
    (net (code "70") (name "unconnected-(LCD1-NC-Pad15)") (class "Default")
      (node (ref "LCD1") (pin "15") (pinfunction "NC_15") (pintype "passive+no_connect"))
    )
    (net (code "71") (name "unconnected-(LCD1-NC-Pad16)") (class "Default")
      (node (ref "LCD1") (pin "16") (pinfunction "NC_16") (pintype "passive+no_connect"))
    )
    (net (code "72") (name "unconnected-(U2A-PA0-WKUP-Pad10)") (class "Default")
      (node (ref "U2") (pin "10") (pinfunction "PA0-WKUP_10") (pintype "bidirectional+no_connect"))
    )
    (net (code "73") (name "unconnected-(U2A-PA7-Pad17)") (class "Default")
      (node (ref "U2") (pin "17") (pinfunction "PA7_17") (pintype "bidirectional+no_connect"))
    )
    (net (code "74") (name "unconnected-(U2A-PA8-Pad29)") (class "Default")
      (node (ref "U2") (pin "29") (pinfunction "PA8_29") (pintype "bidirectional+no_connect"))
    )
    (net (code "75") (name "unconnected-(U2A-PA10-Pad31)") (class "Default")
      (node (ref "U2") (pin "31") (pinfunction "PA10_31") (pintype "bidirectional+no_connect"))
    )
    (net (code "76") (name "unconnected-(U2A-PA11-Pad32)") (class "Default")
      (node (ref "U2") (pin "32") (pinfunction "PA11_32") (pintype "bidirectional+no_connect"))
    )
    (net (code "77") (name "unconnected-(U2A-PA12-Pad33)") (class "Default")
      (node (ref "U2") (pin "33") (pinfunction "PA12_33") (pintype "bidirectional+no_connect"))
    )
    (net (code "78") (name "unconnected-(U2A-PB0-Pad18)") (class "Default")
      (node (ref "U2") (pin "18") (pinfunction "PB0_18") (pintype "bidirectional+no_connect"))
    )
    (net (code "79") (name "unconnected-(U2A-PB2-Pad20)") (class "Default")
      (node (ref "U2") (pin "20") (pinfunction "PB2_20") (pintype "bidirectional+no_connect"))
    )
    (net (code "80") (name "unconnected-(U2A-PB6-Pad42)") (class "Default")
      (node (ref "U2") (pin "42") (pinfunction "PB6_42") (pintype "bidirectional+no_connect"))
    )
    (net (code "81") (name "unconnected-(U2A-PB10-Pad21)") (class "Default")
      (node (ref "U2") (pin "21") (pinfunction "PB10_21") (pintype "bidirectional+no_connect"))
    )
    (net (code "82") (name "unconnected-(U2A-PB12-Pad25)") (class "Default")
      (node (ref "U2") (pin "25") (pinfunction "PB12_25") (pintype "bidirectional+no_connect"))
    )
    (net (code "83") (name "unconnected-(U2A-PB13-Pad26)") (class "Default")
      (node (ref "U2") (pin "26") (pinfunction "PB13_26") (pintype "bidirectional+no_connect"))
    )
    (net (code "84") (name "unconnected-(U2A-PB14-Pad27)") (class "Default")
      (node (ref "U2") (pin "27") (pinfunction "PB14_27") (pintype "bidirectional+no_connect"))
    )
    (net (code "85") (name "unconnected-(U2A-PB15-Pad28)") (class "Default")
      (node (ref "U2") (pin "28") (pinfunction "PB15_28") (pintype "bidirectional+no_connect"))
    )
    (net (code "86") (name "unconnected-(U2A-PC13-Pad2)") (class "Default")
      (node (ref "U2") (pin "2") (pinfunction "PC13_2") (pintype "bidirectional+no_connect"))
    )
    (net (code "87") (name "unconnected-(U2A-PC14-OSC32_IN(PC14)-Pad3)") (class "Default")
      (node (ref "U2") (pin "3") (pinfunction "PC14-OSC32_IN(PC14)_3") (pintype "bidirectional+no_connect"))
    )
    (net (code "88") (name "unconnected-(U2A-PC15-OSC32_OUT(PC15)-Pad4)") (class "Default")
      (node (ref "U2") (pin "4") (pinfunction "PC15-OSC32_OUT(PC15)_4") (pintype "bidirectional+no_connect"))
    )
    (net (code "89") (name "unconnected-(U5-BP-Pad4)") (class "Default")
      (node (ref "U5") (pin "4") (pinfunction "BP_4") (pintype "passive+no_connect"))
    )
  )
)
